# socket_to_header_with_driver.net
KiCad netlist of a schematic drawn in EAGLE
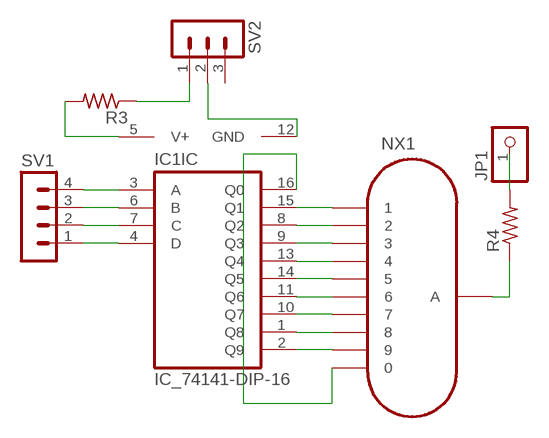
[diagram p0: schematic, sheet 1]

(export (version "E")
  (design (tool "Eeschema 10.0.6"))
  (components
    (comp (ref "IC1")
      (value "IC_74141-DIP-16")
      (footprint "eagle-import:DIL16")
      (libsource (lib "eagle-import") (part "IC_74141-DIP-16"))
    )
    (comp (ref "JP1")
      (value "PINHD-1X1")
      (footprint "eagle-import:1X01")
      (libsource (lib "eagle-import") (part "PINHD-1X1"))
    )
    (comp (ref "NX1")
      (value "IN-12A")
      (footprint "eagle-import:IN-12")
      (libsource (lib "eagle-import") (part "IN-12A"))
    )
    (comp (ref "R3")
      (value "R-US_0204/7")
      (footprint "eagle-import:0204_7")
      (libsource (lib "eagle-import") (part "R-US_0204/7"))
    )
    (comp (ref "R4")
      (value "R-US_0204/7")
      (footprint "eagle-import:0204_7")
      (libsource (lib "eagle-import") (part "R-US_0204/7"))
    )
    (comp (ref "SV1")
      (value "MA04-1")
      (footprint "eagle-import:MA04-1")
      (libsource (lib "eagle-import") (part "MA04-1"))
    )
    (comp (ref "SV2")
      (value "MA03-1")
      (footprint "eagle-import:MA03-1")
      (libsource (lib "eagle-import") (part "MA03-1"))
    )
  )
  (nets
    (net (code "1") (name "Net-(IC1A-A)") (class "Default")
      (node (ref "IC1") (pin "3") (pinfunction "A_3") (pintype "input"))
      (node (ref "SV1") (pin "4") (pinfunction "4_4") (pintype "passive"))
    )
    (net (code "2") (name "Net-(IC1A-B)") (class "Default")
      (node (ref "IC1") (pin "6") (pinfunction "B_6") (pintype "input"))
      (node (ref "SV1") (pin "3") (pinfunction "3_3") (pintype "passive"))
    )
    (net (code "3") (name "Net-(IC1A-C)") (class "Default")
      (node (ref "IC1") (pin "7") (pinfunction "C_7") (pintype "input"))
      (node (ref "SV1") (pin "2") (pinfunction "2_2") (pintype "passive"))
    )
    (net (code "4") (name "Net-(IC1A-D)") (class "Default")
      (node (ref "IC1") (pin "4") (pinfunction "D_4") (pintype "input"))
      (node (ref "SV1") (pin "1") (pinfunction "1_1") (pintype "passive"))
    )
    (net (code "5") (name "Net-(IC1A-Q0)") (class "Default")
      (node (ref "IC1") (pin "16") (pinfunction "Q0_16") (pintype "output"))
      (node (ref "NX1") (pin "0") (pinfunction "0_0") (pintype "bidirectional"))
    )
    (net (code "6") (name "Net-(IC1A-Q1)") (class "Default")
      (node (ref "IC1") (pin "15") (pinfunction "Q1_15") (pintype "output"))
      (node (ref "NX1") (pin "1") (pinfunction "1_1") (pintype "bidirectional"))
    )
    (net (code "7") (name "Net-(IC1A-Q2)") (class "Default")
      (node (ref "IC1") (pin "8") (pinfunction "Q2_8") (pintype "output"))
      (node (ref "NX1") (pin "2") (pinfunction "2_2") (pintype "bidirectional"))
    )
    (net (code "8") (name "Net-(IC1A-Q3)") (class "Default")
      (node (ref "IC1") (pin "9") (pinfunction "Q3_9") (pintype "output"))
      (node (ref "NX1") (pin "3") (pinfunction "3_3") (pintype "bidirectional"))
    )
    (net (code "9") (name "Net-(IC1A-Q4)") (class "Default")
      (node (ref "IC1") (pin "13") (pinfunction "Q4_13") (pintype "output"))
      (node (ref "NX1") (pin "4") (pinfunction "4_4") (pintype "bidirectional"))
    )
    (net (code "10") (name "Net-(IC1A-Q5)") (class "Default")
      (node (ref "IC1") (pin "14") (pinfunction "Q5_14") (pintype "output"))
      (node (ref "NX1") (pin "5") (pinfunction "5_5") (pintype "bidirectional"))
    )
    (net (code "11") (name "Net-(IC1A-Q6)") (class "Default")
      (node (ref "IC1") (pin "11") (pinfunction "Q6_11") (pintype "output"))
      (node (ref "NX1") (pin "6") (pinfunction "6_6") (pintype "bidirectional"))
    )
    (net (code "12") (name "Net-(IC1A-Q7)") (class "Default")
      (node (ref "IC1") (pin "10") (pinfunction "Q7_10") (pintype "output"))
      (node (ref "NX1") (pin "7") (pinfunction "7_7") (pintype "bidirectional"))
    )
    (net (code "13") (name "Net-(IC1A-Q8)") (class "Default")
      (node (ref "IC1") (pin "1") (pinfunction "Q8_1") (pintype "output"))
      (node (ref "NX1") (pin "8") (pinfunction "8_8") (pintype "bidirectional"))
    )
    (net (code "14") (name "Net-(IC1A-Q9)") (class "Default")
      (node (ref "IC1") (pin "2") (pinfunction "Q9_2") (pintype "output"))
      (node (ref "NX1") (pin "9") (pinfunction "9_9") (pintype "bidirectional"))
    )
    (net (code "15") (name "Net-(IC1B-GND)") (class "Default")
      (node (ref "IC1") (pin "12") (pinfunction "GND_12") (pintype "power_in"))
      (node (ref "SV2") (pin "2") (pinfunction "2_2") (pintype "passive"))
    )
    (net (code "16") (name "Net-(IC1B-V+)") (class "Default")
      (node (ref "IC1") (pin "5") (pinfunction "V+_5") (pintype "power_in"))
      (node (ref "R3") (pin "2") (pinfunction "2_2") (pintype "passive"))
    )
    (net (code "17") (name "Net-(JP1-Pad1)") (class "Default")
      (node (ref "JP1") (pin "1") (pinfunction "1_1") (pintype "passive"))
      (node (ref "R4") (pin "2") (pinfunction "2_2") (pintype "passive"))
    )
    (net (code "18") (name "Net-(NX1-PadA)") (class "Default")
      (node (ref "NX1") (pin "A") (pinfunction "A_A") (pintype "bidirectional"))
      (node (ref "R4") (pin "1") (pinfunction "1_1") (pintype "passive"))
    )
    (net (code "19") (name "Net-(R3-Pad1)") (class "Default")
      (node (ref "R3") (pin "1") (pinfunction "1_1") (pintype "passive"))
      (node (ref "SV2") (pin "1") (pinfunction "1_1") (pintype "passive"))
    )
    (net (code "20") (name "unconnected-(SV2-Pad3)") (class "Default")
      (node (ref "SV2") (pin "3") (pinfunction "3_3") (pintype "passive"))
    )
  )
)
